# eagle_designV3.net
KiCad netlist of a schematic drawn in EAGLE
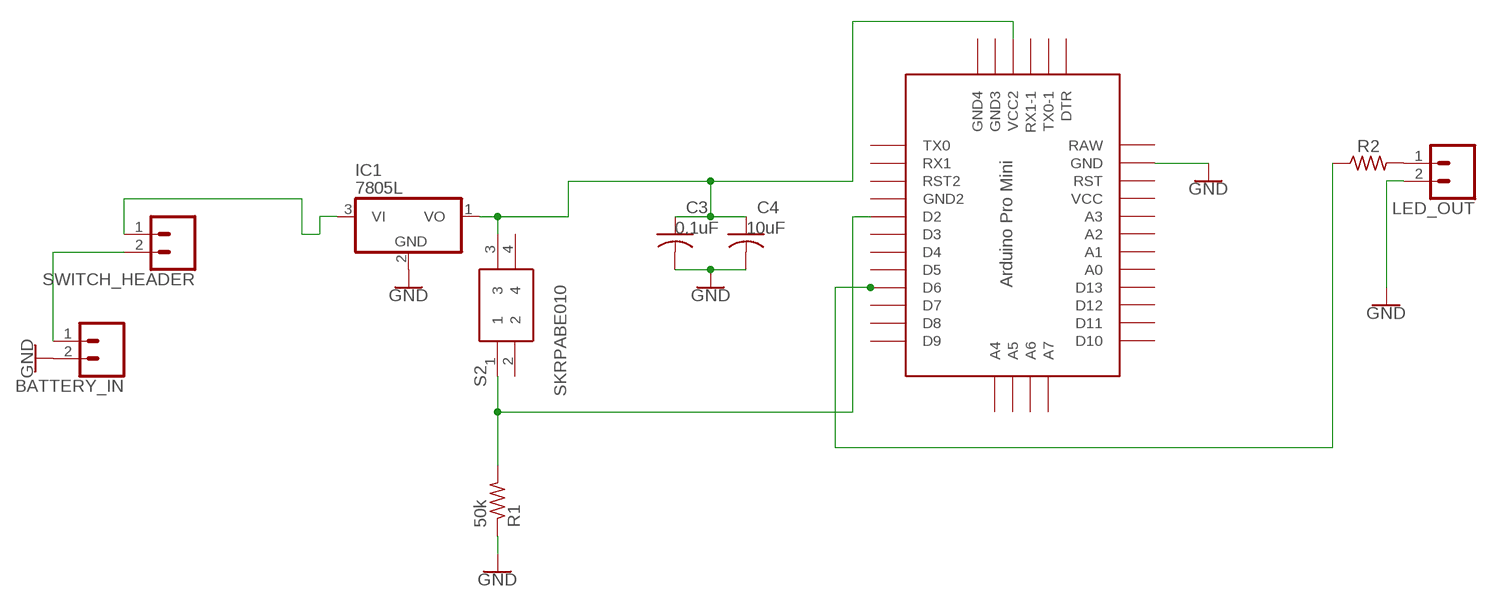
[diagram p0: schematic, sheet 1]

(export (version "E")
  (design (tool "Eeschema 10.0.6"))
  (components
    (comp (ref "BATTERY_IN")
      (value "CONN_02")
      (footprint "eagle-import:1X02")
      (libsource (lib "eagle-import") (part "CONN_02"))
    )
    (comp (ref "C3")
      (value "0.1uF")
      (footprint "eagle-import:C0805")
      (fields (field (name "CAP") "0.1uF"))
      (libsource (lib "eagle-import") (part "C-USC0805"))
    )
    (comp (ref "C4")
      (value "10uF")
      (footprint "eagle-import:C0805")
      (fields (field (name "CAP") "10uF"))
      (libsource (lib "eagle-import") (part "C-USC0805"))
    )
    (comp (ref "IC1")
      (value "7805L")
      (footprint "eagle-import:TO92")
      (libsource (lib "eagle-import") (part "78L05"))
    )
    (comp (ref "LED_OUT")
      (value "CONN_02")
      (footprint "eagle-import:1X02")
      (libsource (lib "eagle-import") (part "CONN_02"))
    )
    (comp (ref "R1")
      (value "50k")
      (footprint "eagle-import:R0805")
      (libsource (lib "eagle-import") (part "R-US_R0805"))
    )
    (comp (ref "R2")
      (value "330")
      (footprint "eagle-import:R0805")
      (libsource (lib "eagle-import") (part "R-US_R0805"))
    )
    (comp (ref "S2")
      (value "SKRPABE010")
      (footprint "eagle-import:SMT(4.2X3.2)")
      (fields (field (name "MOUSER_PART_NUMBER") "688-SKRPAB"))
      (libsource (lib "eagle-import") (part "SKRPABE010"))
    )
    (comp (ref "SWITCH_HEADER")
      (value "CONN_02")
      (footprint "eagle-import:1X02")
      (libsource (lib "eagle-import") (part "CONN_02"))
    )
    (comp (ref "U$1")
      (value "PRO-MINI")
      (footprint "eagle-import:PRO-MINI")
      (libsource (lib "eagle-import") (part "PRO-MINI"))
    )
  )
  (nets
    (net (code "1") (name "/RAW") (class "Default")
      (node (ref "U$1") (pin "RAW") (pinfunction "RAW_RAW") (pintype "power_in"))
    )
    (net (code "2") (name "GND") (class "Default")
      (node (ref "BATTERY_IN") (pin "2") (pinfunction "2_2") (pintype "passive"))
      (node (ref "C3") (pin "2") (pinfunction "2_2") (pintype "passive"))
      (node (ref "C4") (pin "2") (pinfunction "2_2") (pintype "passive"))
      (node (ref "IC1") (pin "2") (pinfunction "GND_2") (pintype "passive"))
      (node (ref "LED_OUT") (pin "2") (pinfunction "2_2") (pintype "passive"))
      (node (ref "R1") (pin "1") (pinfunction "1_1") (pintype "passive"))
      (node (ref "U$1") (pin "GND") (pinfunction "GND_GND") (pintype "input"))
    )
    (net (code "3") (name "Net-(BATTERY_IN-Pad1)") (class "Default")
      (node (ref "BATTERY_IN") (pin "1") (pinfunction "1_1") (pintype "passive"))
      (node (ref "SWITCH_HEADER") (pin "2") (pinfunction "2_2") (pintype "passive"))
    )
    (net (code "4") (name "Net-(IC1-VI)") (class "Default")
      (node (ref "IC1") (pin "3") (pinfunction "VI_3") (pintype "input"))
      (node (ref "SWITCH_HEADER") (pin "1") (pinfunction "1_1") (pintype "passive"))
    )
    (net (code "5") (name "Net-(IC1-VO)") (class "Default")
      (node (ref "C3") (pin "1") (pinfunction "1_1") (pintype "passive"))
      (node (ref "C4") (pin "1") (pinfunction "1_1") (pintype "passive"))
      (node (ref "IC1") (pin "1") (pinfunction "VO_1") (pintype "passive"))
      (node (ref "S2") (pin "3") (pinfunction "3_3") (pintype "bidirectional"))
      (node (ref "U$1") (pin "VCC1") (pinfunction "VCC2_VCC1") (pintype "bidirectional"))
    )
    (net (code "6") (name "Net-(LED_OUT-Pad1)") (class "Default")
      (node (ref "LED_OUT") (pin "1") (pinfunction "1_1") (pintype "passive"))
      (node (ref "R2") (pin "2") (pinfunction "2_2") (pintype "passive"))
    )
    (net (code "7") (name "Net-(R1-Pad2)") (class "Default")
      (node (ref "R1") (pin "2") (pinfunction "2_2") (pintype "passive"))
      (node (ref "S2") (pin "1") (pinfunction "1_1") (pintype "bidirectional"))
      (node (ref "U$1") (pin "D2") (pinfunction "D2_D2") (pintype "bidirectional"))
    )
    (net (code "8") (name "Net-(R2-Pad1)") (class "Default")
      (node (ref "R2") (pin "1") (pinfunction "1_1") (pintype "passive"))
      (node (ref "U$1") (pin "D6") (pinfunction "D6_D6") (pintype "bidirectional"))
    )
    (net (code "9") (name "unconnected-(S2-Pad2)") (class "Default")
      (node (ref "S2") (pin "2") (pinfunction "2_2") (pintype "bidirectional"))
    )
    (net (code "10") (name "unconnected-(S2-Pad4)") (class "Default")
      (node (ref "S2") (pin "4") (pinfunction "4_4") (pintype "bidirectional"))
    )
    (net (code "11") (name "unconnected-(U$1-GND2-PadGND1)") (class "Default")
      (node (ref "U$1") (pin "GND1") (pinfunction "GND2_GND1") (pintype "bidirectional"))
    )
    (net (code "12") (name "unconnected-(U$1-GND4-PadGND2)") (class "Default")
      (node (ref "U$1") (pin "GND2") (pinfunction "GND4_GND2") (pintype "bidirectional"))
    )
    (net (code "13") (name "unconnected-(U$1-PadA0)") (class "Default")
      (node (ref "U$1") (pin "A0") (pinfunction "A0_A0") (pintype "bidirectional"))
    )
    (net (code "14") (name "unconnected-(U$1-PadA1)") (class "Default")
      (node (ref "U$1") (pin "A1") (pinfunction "A1_A1") (pintype "bidirectional"))
    )
    (net (code "15") (name "unconnected-(U$1-PadA2)") (class "Default")
      (node (ref "U$1") (pin "A2") (pinfunction "A2_A2") (pintype "bidirectional"))
    )
    (net (code "16") (name "unconnected-(U$1-PadA3)") (class "Default")
      (node (ref "U$1") (pin "A3") (pinfunction "A3_A3") (pintype "bidirectional"))
    )
    (net (code "17") (name "unconnected-(U$1-PadA4)") (class "Default")
      (node (ref "U$1") (pin "A4") (pinfunction "A4_A4") (pintype "bidirectional"))
    )
    (net (code "18") (name "unconnected-(U$1-PadA5)") (class "Default")
      (node (ref "U$1") (pin "A5") (pinfunction "A5_A5") (pintype "bidirectional"))
    )
    (net (code "19") (name "unconnected-(U$1-PadA6)") (class "Default")
      (node (ref "U$1") (pin "A6") (pinfunction "A6_A6") (pintype "bidirectional"))
    )
    (net (code "20") (name "unconnected-(U$1-PadA7)") (class "Default")
      (node (ref "U$1") (pin "A7") (pinfunction "A7_A7") (pintype "bidirectional"))
    )
    (net (code "21") (name "unconnected-(U$1-PadD3)") (class "Default")
      (node (ref "U$1") (pin "D3") (pinfunction "D3_D3") (pintype "bidirectional"))
    )
    (net (code "22") (name "unconnected-(U$1-PadD4)") (class "Default")
      (node (ref "U$1") (pin "D4") (pinfunction "D4_D4") (pintype "bidirectional"))
    )
    (net (code "23") (name "unconnected-(U$1-PadD5)") (class "Default")
      (node (ref "U$1") (pin "D5") (pinfunction "D5_D5") (pintype "bidirectional"))
    )
    (net (code "24") (name "unconnected-(U$1-PadD7)") (class "Default")
      (node (ref "U$1") (pin "D7") (pinfunction "D7_D7") (pintype "bidirectional"))
    )
    (net (code "25") (name "unconnected-(U$1-PadD8)") (class "Default")
      (node (ref "U$1") (pin "D8") (pinfunction "D8_D8") (pintype "bidirectional"))
    )
    (net (code "26") (name "unconnected-(U$1-PadD9)") (class "Default")
      (node (ref "U$1") (pin "D9") (pinfunction "D9_D9") (pintype "bidirectional"))
    )
    (net (code "27") (name "unconnected-(U$1-PadD10)") (class "Default")
      (node (ref "U$1") (pin "D10") (pinfunction "D10_D10") (pintype "bidirectional"))
    )
    (net (code "28") (name "unconnected-(U$1-PadD11)") (class "Default")
      (node (ref "U$1") (pin "D11") (pinfunction "D11_D11") (pintype "bidirectional"))
    )
    (net (code "29") (name "unconnected-(U$1-PadD12)") (class "Default")
      (node (ref "U$1") (pin "D12") (pinfunction "D12_D12") (pintype "bidirectional"))
    )
    (net (code "30") (name "unconnected-(U$1-PadD13)") (class "Default")
      (node (ref "U$1") (pin "D13") (pinfunction "D13_D13") (pintype "bidirectional"))
    )
    (net (code "31") (name "unconnected-(U$1-PadDTR)") (class "Default")
      (node (ref "U$1") (pin "DTR") (pinfunction "DTR_DTR") (pintype "bidirectional"))
    )
    (net (code "32") (name "unconnected-(U$1-PadGND3)") (class "Default")
      (node (ref "U$1") (pin "GND3") (pinfunction "GND3_GND3") (pintype "bidirectional"))
    )
    (net (code "33") (name "unconnected-(U$1-PadRST)") (class "Default")
      (node (ref "U$1") (pin "RST") (pinfunction "RST_RST") (pintype "bidirectional"))
    )
    (net (code "34") (name "unconnected-(U$1-PadRX1)") (class "Default")
      (node (ref "U$1") (pin "RX1") (pinfunction "RX1_RX1") (pintype "bidirectional"))
    )
    (net (code "35") (name "unconnected-(U$1-PadRX1-1)") (class "Default")
      (node (ref "U$1") (pin "RX1-1") (pinfunction "RX1-1_RX1-1") (pintype "bidirectional"))
    )
    (net (code "36") (name "unconnected-(U$1-PadTX0)") (class "Default")
      (node (ref "U$1") (pin "TX0") (pinfunction "TX0_TX0") (pintype "bidirectional"))
    )
    (net (code "37") (name "unconnected-(U$1-PadTX0-1)") (class "Default")
      (node (ref "U$1") (pin "TX0-1") (pinfunction "TX0-1_TX0-1") (pintype "bidirectional"))
    )
    (net (code "38") (name "unconnected-(U$1-PadVCC)") (class "Default")
      (node (ref "U$1") (pin "VCC") (pinfunction "VCC_VCC") (pintype "bidirectional"))
    )
    (net (code "39") (name "unconnected-(U$1-RST2-PadRST1)") (class "Default")
      (node (ref "U$1") (pin "RST1") (pinfunction "RST2_RST1") (pintype "bidirectional"))
    )
  )
)
